# hand_shank.net
KiCad netlist of a schematic drawn in Altium Designer
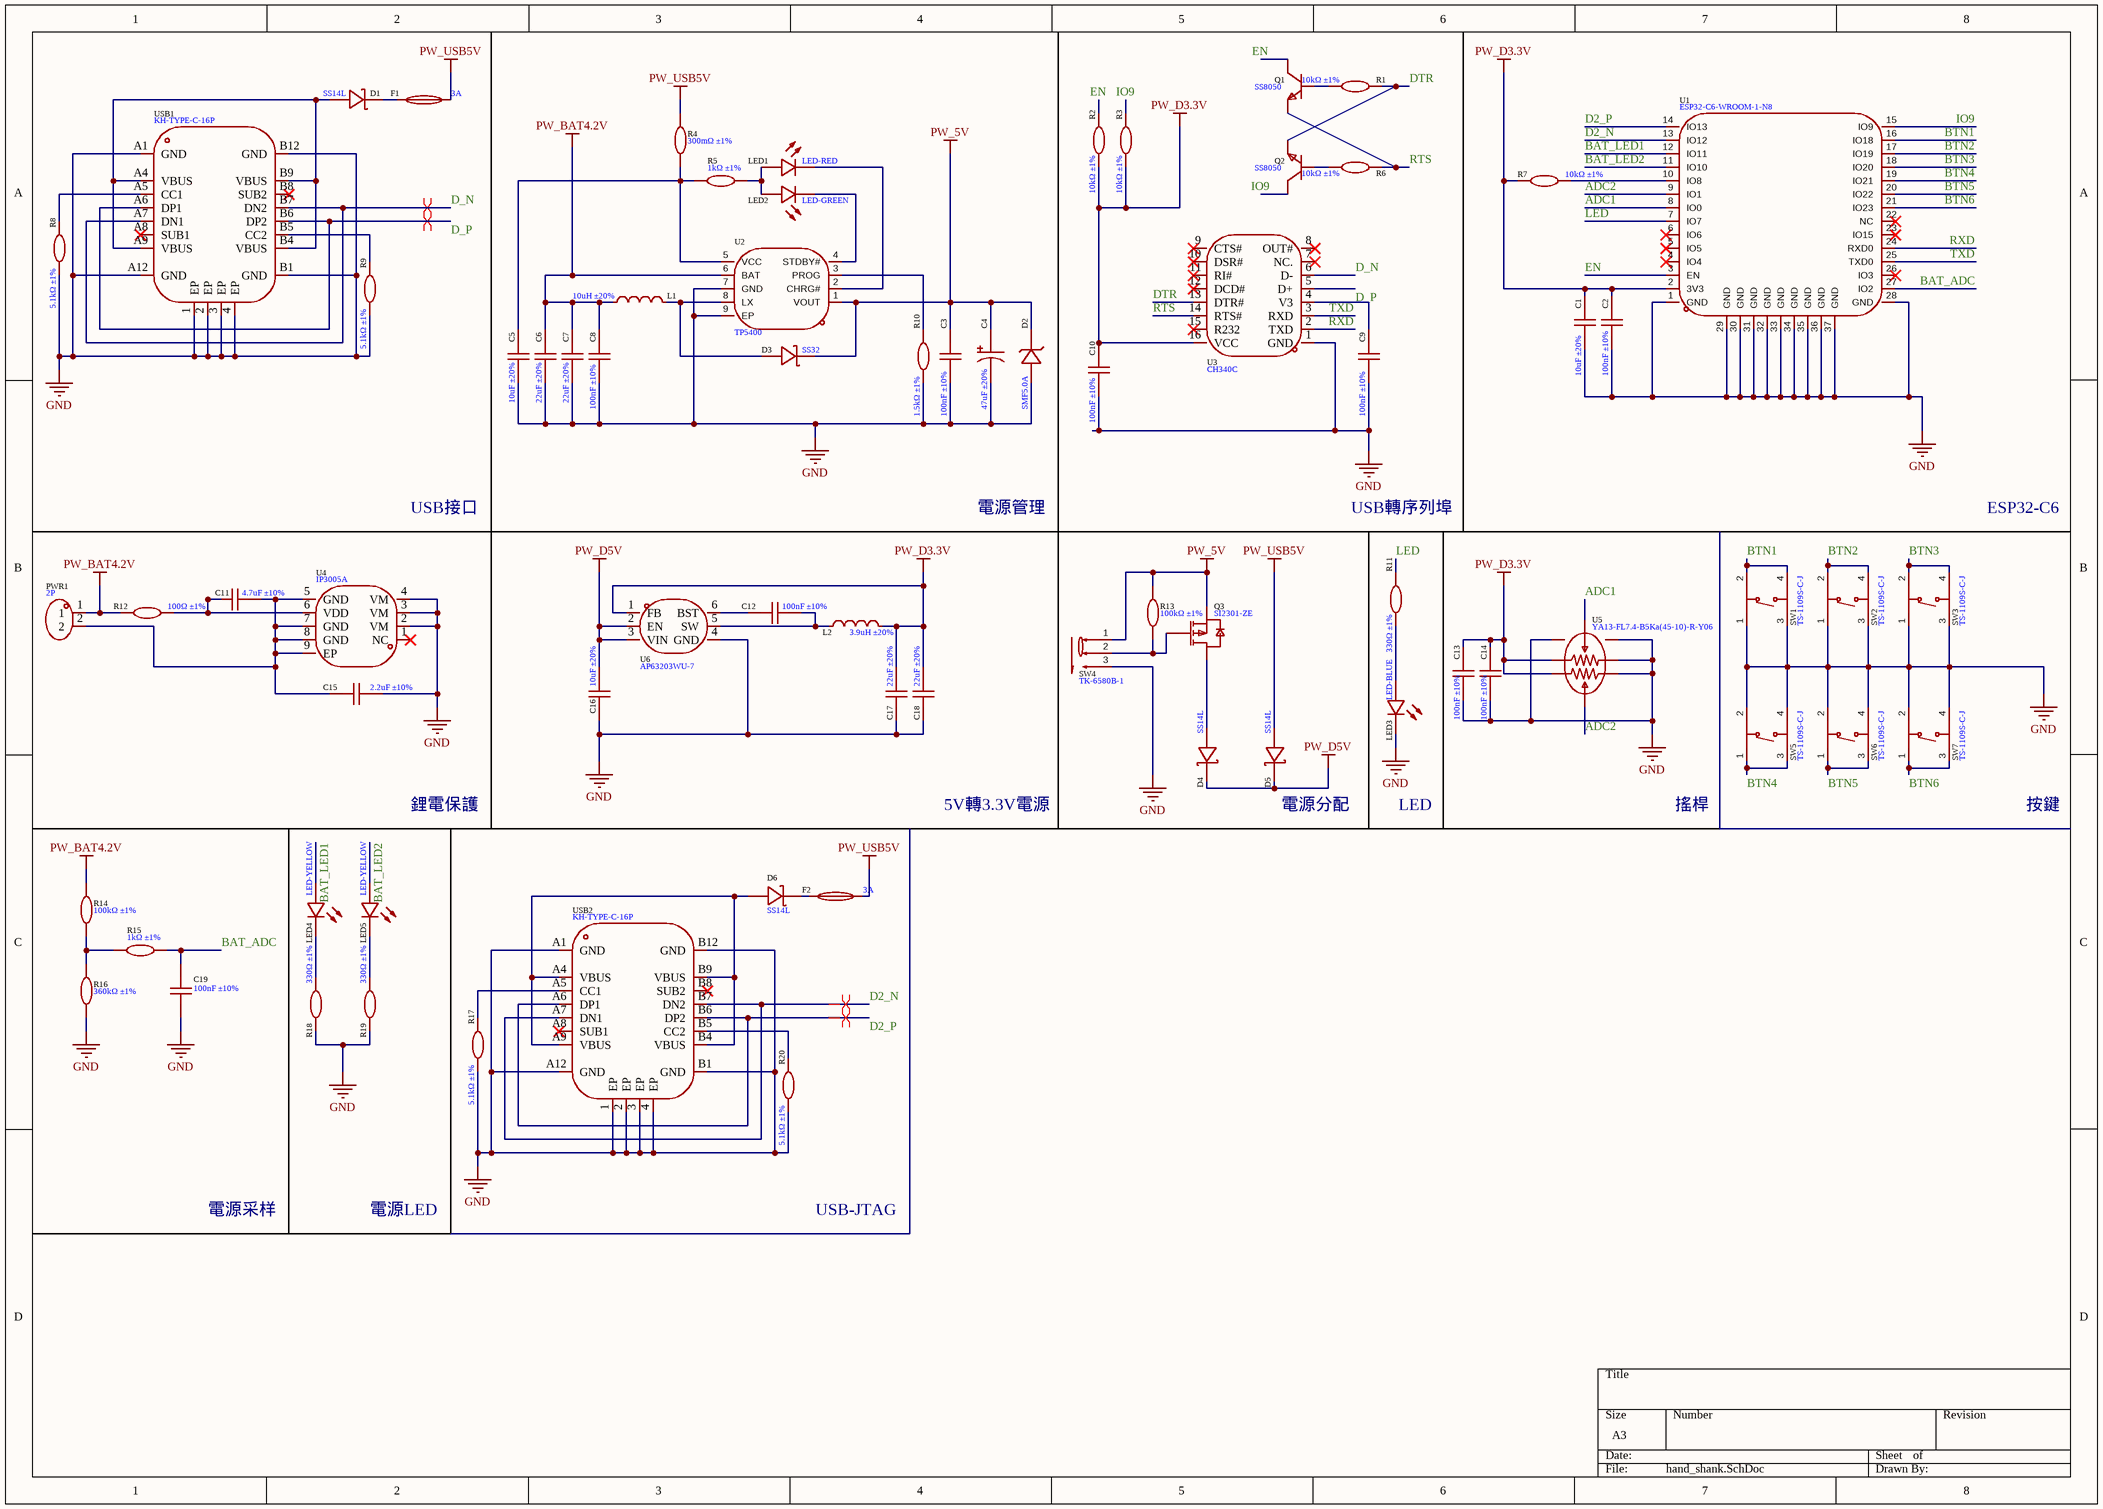
[diagram p0: hand_shank.SchDoc]

(export (version "E")
  (design (tool "Eeschema 10.0.6"))
  (components
    (comp (ref "C1")
      (value "10uF ±20%")
      (footprint "C0603")
      (fields (field (name "MANUFACTURER_PART") "CL10A106MA8NRNC") (field (name "MANUFACTURER") "SAMSUNG"))
      (libsource (lib "Database_Libs") (part "CAP"))
    )
    (comp (ref "C2")
      (value "100nF ±10%")
      (footprint "C0603")
      (fields (field (name "MANUFACTURER_PART") "CL10B104KB8NNNC") (field (name "MANUFACTURER") "SAMSUNG"))
      (libsource (lib "Database_Libs") (part "CAP"))
    )
    (comp (ref "C3")
      (value "100nF ±10%")
      (footprint "C0603")
      (fields (field (name "MANUFACTURER_PART") "CL10B104KB8NNNC") (field (name "MANUFACTURER") "SAMSUNG"))
      (libsource (lib "Database_Libs") (part "CAP"))
    )
    (comp (ref "C4")
      (value "47uF ±20%")
      (footprint "CAP-SMD_BD6.3-L6.5-W6.5-LS7.2-FD")
      (fields (field (name "MANUFACTURER_PART") "RVE25V47M6X5") (field (name "MANUFACTURER") "JIERR"))
      (libsource (lib "Database_Libs") (part "CAP-POL"))
    )
    (comp (ref "C5")
      (value "10uF ±20%")
      (footprint "C0603")
      (fields (field (name "MANUFACTURER_PART") "CL10A106MA8NRNC") (field (name "MANUFACTURER") "SAMSUNG"))
      (libsource (lib "Database_Libs") (part "CAP"))
    )
    (comp (ref "C6")
      (value "22uF ±20%")
      (footprint "C0805")
      (fields (field (name "MANUFACTURER_PART") "CL21A226MAQNNNE") (field (name "MANUFACTURER") "SAMSUNG"))
      (libsource (lib "Database_Libs") (part "CAP"))
    )
    (comp (ref "C7")
      (value "22uF ±20%")
      (footprint "C0805")
      (fields (field (name "MANUFACTURER_PART") "CL21A226MAQNNNE") (field (name "MANUFACTURER") "SAMSUNG"))
      (libsource (lib "Database_Libs") (part "CAP"))
    )
    (comp (ref "C8")
      (value "100nF ±10%")
      (footprint "C0603")
      (fields (field (name "MANUFACTURER_PART") "CL10B104KB8NNNC") (field (name "MANUFACTURER") "SAMSUNG"))
      (libsource (lib "Database_Libs") (part "CAP"))
    )
    (comp (ref "C9")
      (value "100nF ±10%")
      (footprint "C0603")
      (fields (field (name "MANUFACTURER_PART") "CL10B104KB8NNNC") (field (name "MANUFACTURER") "SAMSUNG"))
      (libsource (lib "Database_Libs") (part "CAP"))
    )
    (comp (ref "C10")
      (value "100nF ±10%")
      (footprint "C0603")
      (fields (field (name "MANUFACTURER_PART") "CL10B104KB8NNNC") (field (name "MANUFACTURER") "SAMSUNG"))
      (libsource (lib "Database_Libs") (part "CAP"))
    )
    (comp (ref "C11")
      (value "4.7uF ±10%")
      (footprint "C0603")
      (fields (field (name "MANUFACTURER_PART") "CL10A475KO8NNNC") (field (name "MANUFACTURER") "SAMSUNG"))
      (libsource (lib "Database_Libs") (part "CAP"))
    )
    (comp (ref "C12")
      (value "100nF ±10%")
      (footprint "C0603")
      (fields (field (name "MANUFACTURER_PART") "CL10B104KB8NNNC") (field (name "MANUFACTURER") "SAMSUNG"))
      (libsource (lib "Database_Libs") (part "CAP"))
    )
    (comp (ref "C13")
      (value "100nF ±10%")
      (footprint "C0603")
      (fields (field (name "MANUFACTURER_PART") "CL10B104KB8NNNC") (field (name "MANUFACTURER") "SAMSUNG"))
      (libsource (lib "Database_Libs") (part "CAP"))
    )
    (comp (ref "C14")
      (value "100nF ±10%")
      (footprint "C0603")
      (fields (field (name "MANUFACTURER_PART") "CL10B104KB8NNNC") (field (name "MANUFACTURER") "SAMSUNG"))
      (libsource (lib "Database_Libs") (part "CAP"))
    )
    (comp (ref "C15")
      (value "2.2uF ±10%")
      (footprint "C0603")
      (fields (field (name "MANUFACTURER_PART") "CL10A225KB8NNNC") (field (name "MANUFACTURER") "SAMSUNG"))
      (libsource (lib "Database_Libs") (part "CAP"))
    )
    (comp (ref "C16")
      (value "10uF ±20%")
      (footprint "C0603")
      (fields (field (name "MANUFACTURER_PART") "CL10A106MA8NRNC") (field (name "MANUFACTURER") "SAMSUNG"))
      (libsource (lib "Database_Libs") (part "CAP"))
    )
    (comp (ref "C17")
      (value "22uF ±20%")
      (footprint "C0805")
      (fields (field (name "MANUFACTURER_PART") "CL21A226MAQNNNE") (field (name "MANUFACTURER") "SAMSUNG"))
      (libsource (lib "Database_Libs") (part "CAP"))
    )
    (comp (ref "C18")
      (value "22uF ±20%")
      (footprint "C0805")
      (fields (field (name "MANUFACTURER_PART") "CL21A226MAQNNNE") (field (name "MANUFACTURER") "SAMSUNG"))
      (libsource (lib "Database_Libs") (part "CAP"))
    )
    (comp (ref "C19")
      (value "100nF ±10%")
      (footprint "C0603")
      (fields (field (name "MANUFACTURER_PART") "CL10B104KB8NNNC") (field (name "MANUFACTURER") "SAMSUNG"))
      (libsource (lib "Database_Libs") (part "CAP"))
    )
    (comp (ref "D1")
      (value "SS14L")
      (footprint "SOD-123F_L2.8-W1.8-LS3.7-RD")
      (fields (field (name "MANUFACTURER") "Hottech"))
      (libsource (lib "Database_Libs") (part "DIODE-SCHOTTKY"))
    )
    (comp (ref "D2")
      (value "SMF5.0A")
      (footprint "SOD-123FL_L2.7-W1.8-LS3.8-RD")
      (fields (field (name "MANUFACTURER") "R+O"))
      (libsource (lib "Database_Libs") (part "DIODE-TVS"))
    )
    (comp (ref "D3")
      (value "SS32")
      (footprint "SMA_L4.3-W2.6-LS5.0-RD")
      (fields (field (name "MANUFACTURER") "R+O"))
      (libsource (lib "Database_Libs") (part "DIODE-SCHOTTKY"))
    )
    (comp (ref "D4")
      (value "SS14L")
      (footprint "SOD-123F_L2.8-W1.8-LS3.7-RD")
      (fields (field (name "MANUFACTURER") "Hottech"))
      (libsource (lib "Database_Libs") (part "DIODE-SCHOTTKY"))
    )
    (comp (ref "D5")
      (value "SS14L")
      (footprint "SOD-123F_L2.8-W1.8-LS3.7-RD")
      (fields (field (name "MANUFACTURER") "Hottech"))
      (libsource (lib "Database_Libs") (part "DIODE-SCHOTTKY"))
    )
    (comp (ref "D6")
      (value "SS14L")
      (footprint "SOD-123F_L2.8-W1.8-LS3.7-RD")
      (fields (field (name "MANUFACTURER") "Hottech"))
      (libsource (lib "Database_Libs") (part "DIODE-SCHOTTKY"))
    )
    (comp (ref "F1")
      (value "3A")
      (footprint "F1206")
      (fields (field (name "MANUFACTURER_PART") "12H1300C") (field (name "MANUFACTURER") "LANSON"))
      (libsource (lib "Database_Libs") (part "FUSE"))
    )
    (comp (ref "F2")
      (value "3A")
      (footprint "F1206")
      (fields (field (name "MANUFACTURER_PART") "12H1300C") (field (name "MANUFACTURER") "LANSON"))
      (libsource (lib "Database_Libs") (part "FUSE"))
    )
    (comp (ref "L1")
      (value "10uH ±20%")
      (footprint "IND-SMD_L7.3-W6.8")
      (fields (field (name "MANUFACTURER_PART") "FXL0630-100-M") (field (name "MANUFACTURER") "cjiang"))
      (libsource (lib "Database_Libs") (part "IND"))
    )
    (comp (ref "L2")
      (value "3.9uH ±20%")
      (footprint "IND-SMD_L4.0-W4.0_FNR40XXS")
      (fields (field (name "MANUFACTURER_PART") "FNR4030S3R9MT") (field (name "MANUFACTURER") "cjiang"))
      (libsource (lib "Database_Libs") (part "IND"))
    )
    (comp (ref "LED1")
      (value "LED-RED")
      (footprint "LED0603-RD")
      (fields (field (name "MANUFACTURER_PART") "NCD0603R1") (field (name "MANUFACTURER") "nationstar"))
      (libsource (lib "Database_Libs") (part "LED"))
    )
    (comp (ref "LED2")
      (value "LED-GREEN")
      (footprint "LED0603-RD")
      (fields (field (name "MANUFACTURER_PART") "NCD0603G1") (field (name "MANUFACTURER") "nationstar"))
      (libsource (lib "Database_Libs") (part "LED"))
    )
    (comp (ref "LED3")
      (value "LED-BLUE")
      (footprint "LED0603-RD")
      (fields (field (name "MANUFACTURER_PART") "NCD0603B1") (field (name "MANUFACTURER") "nationstar"))
      (libsource (lib "Database_Libs") (part "LED"))
    )
    (comp (ref "LED4")
      (value "LED-YELLOW")
      (footprint "LED0603-RD")
      (fields (field (name "MANUFACTURER_PART") "NCD0603Y1") (field (name "MANUFACTURER") "nationstar"))
      (libsource (lib "Database_Libs") (part "LED"))
    )
    (comp (ref "LED5")
      (value "LED-YELLOW")
      (footprint "LED0603-RD")
      (fields (field (name "MANUFACTURER_PART") "NCD0603Y1") (field (name "MANUFACTURER") "nationstar"))
      (libsource (lib "Database_Libs") (part "LED"))
    )
    (comp (ref "PWR1")
      (value "2P")
      (footprint "CONN-TH_HC-C5080-2AS")
      (fields (field (name "MANUFACTURER_PART") "HC-C5080-2AS") (field (name "MANUFACTURER") "HCTL"))
      (libsource (lib "Database_Libs") (part "CONN-power-2P"))
    )
    (comp (ref "Q1")
      (value "SS8050")
      (footprint "SOT-23-3")
      (fields (field (name "MANUFACTURER") "AnBon"))
      (libsource (lib "Database_Libs") (part "NPN-1B2E3C"))
    )
    (comp (ref "Q2")
      (value "SS8050")
      (footprint "SOT-23-3")
      (fields (field (name "MANUFACTURER") "AnBon"))
      (libsource (lib "Database_Libs") (part "NPN-1B2E3C"))
    )
    (comp (ref "Q3")
      (value "SI2301-ZE")
      (footprint "SOT-23-3")
      (fields (field (name "MANUFACTURER") "HXY"))
      (libsource (lib "Database_Libs") (part "PMOS-1G2S3D"))
    )
    (comp (ref "R1")
      (value "10kΩ ±1%")
      (footprint "R0603")
      (fields (field (name "MANUFACTURER_PART") "0603WAF1002T5E") (field (name "MANUFACTURER") "UNI-ROYAL"))
      (libsource (lib "Database_Libs") (part "RES"))
    )
    (comp (ref "R2")
      (value "10kΩ ±1%")
      (footprint "R0603")
      (fields (field (name "MANUFACTURER_PART") "0603WAF1002T5E") (field (name "MANUFACTURER") "UNI-ROYAL"))
      (libsource (lib "Database_Libs") (part "RES"))
    )
    (comp (ref "R3")
      (value "10kΩ ±1%")
      (footprint "R0603")
      (fields (field (name "MANUFACTURER_PART") "0603WAF1002T5E") (field (name "MANUFACTURER") "UNI-ROYAL"))
      (libsource (lib "Database_Libs") (part "RES"))
    )
    (comp (ref "R4")
      (value "300mΩ ±1%")
      (footprint "R1206")
      (fields
        (field (name "MANUFACTURER_PART") "HoYH1206-1W-300mR-1%")
        (field (name "MANUFACTURER") "Milliohm")
      )
      (libsource (lib "Database_Libs") (part "RES"))
    )
    (comp (ref "R5")
      (value "1kΩ ±1%")
      (footprint "R0603")
      (fields (field (name "MANUFACTURER_PART") "0603WAF1001T5E") (field (name "MANUFACTURER") "UNI-ROYAL"))
      (libsource (lib "Database_Libs") (part "RES"))
    )
    (comp (ref "R6")
      (value "10kΩ ±1%")
      (footprint "R0603")
      (fields (field (name "MANUFACTURER_PART") "0603WAF1002T5E") (field (name "MANUFACTURER") "UNI-ROYAL"))
      (libsource (lib "Database_Libs") (part "RES"))
    )
    (comp (ref "R7")
      (value "10kΩ ±1%")
      (footprint "R0603")
      (fields (field (name "MANUFACTURER_PART") "0603WAF1002T5E") (field (name "MANUFACTURER") "UNI-ROYAL"))
      (libsource (lib "Database_Libs") (part "RES"))
    )
    (comp (ref "R8")
      (value "5.1kΩ ±1%")
      (footprint "R0603")
      (fields (field (name "MANUFACTURER_PART") "0603WAF5101T5E") (field (name "MANUFACTURER") "UNI-ROYAL"))
      (libsource (lib "Database_Libs") (part "RES"))
    )
    (comp (ref "R9")
      (value "5.1kΩ ±1%")
      (footprint "R0603")
      (fields (field (name "MANUFACTURER_PART") "0603WAF5101T5E") (field (name "MANUFACTURER") "UNI-ROYAL"))
      (libsource (lib "Database_Libs") (part "RES"))
    )
    (comp (ref "R10")
      (value "1.5kΩ ±1%")
      (footprint "R0603")
      (fields (field (name "MANUFACTURER_PART") "0603WAF1501T5E") (field (name "MANUFACTURER") "UNI-ROYAL"))
      (libsource (lib "Database_Libs") (part "RES"))
    )
    (comp (ref "R11")
      (value "330Ω ±1%")
      (footprint "R0603")
      (fields (field (name "MANUFACTURER_PART") "0603WAF3300T5E") (field (name "MANUFACTURER") "UNI-ROYAL"))
      (libsource (lib "Database_Libs") (part "RES"))
    )
    (comp (ref "R12")
      (value "100Ω ±1%")
      (footprint "R0603")
      (fields (field (name "MANUFACTURER_PART") "0603WAF1000T5E") (field (name "MANUFACTURER") "UNI-ROYAL"))
      (libsource (lib "Database_Libs") (part "RES"))
    )
    (comp (ref "R13")
      (value "100kΩ ±1%")
      (footprint "R0603")
      (fields (field (name "MANUFACTURER_PART") "0603WAF1003T5E") (field (name "MANUFACTURER") "UNI-ROYAL"))
      (libsource (lib "Database_Libs") (part "RES"))
    )
    (comp (ref "R14")
      (value "100kΩ ±1%")
      (footprint "R0603")
      (fields (field (name "MANUFACTURER_PART") "0603WAF1003T5E") (field (name "MANUFACTURER") "UNI-ROYAL"))
      (libsource (lib "Database_Libs") (part "RES"))
    )
    (comp (ref "R15")
      (value "1kΩ ±1%")
      (footprint "R0603")
      (fields (field (name "MANUFACTURER_PART") "0603WAF1001T5E") (field (name "MANUFACTURER") "UNI-ROYAL"))
      (libsource (lib "Database_Libs") (part "RES"))
    )
    (comp (ref "R16")
      (value "360kΩ ±1%")
      (footprint "R0603")
      (fields (field (name "MANUFACTURER_PART") "0603WAF3603T5E") (field (name "MANUFACTURER") "UNI-ROYAL"))
      (libsource (lib "Database_Libs") (part "RES"))
    )
    (comp (ref "R17")
      (value "5.1kΩ ±1%")
      (footprint "R0603")
      (fields (field (name "MANUFACTURER_PART") "0603WAF5101T5E") (field (name "MANUFACTURER") "UNI-ROYAL"))
      (libsource (lib "Database_Libs") (part "RES"))
    )
    (comp (ref "R18")
      (value "330Ω ±1%")
      (footprint "R0603")
      (fields (field (name "MANUFACTURER_PART") "0603WAF3300T5E") (field (name "MANUFACTURER") "UNI-ROYAL"))
      (libsource (lib "Database_Libs") (part "RES"))
    )
    (comp (ref "R19")
      (value "330Ω ±1%")
      (footprint "R0603")
      (fields (field (name "MANUFACTURER_PART") "0603WAF3300T5E") (field (name "MANUFACTURER") "UNI-ROYAL"))
      (libsource (lib "Database_Libs") (part "RES"))
    )
    (comp (ref "R20")
      (value "5.1kΩ ±1%")
      (footprint "R0603")
      (fields (field (name "MANUFACTURER_PART") "0603WAF5101T5E") (field (name "MANUFACTURER") "UNI-ROYAL"))
      (libsource (lib "Database_Libs") (part "RES"))
    )
    (comp (ref "SW1")
      (value "TS-1109S-C-J")
      (footprint "SW-SMD_4P-L4.5-W4.5-P3.00-LS7.0")
      (fields (field (name "MANUFACTURER") "XKB Connection"))
      (libsource (lib "Database_Libs") (part "SW-PTS-2x2"))
    )
    (comp (ref "SW2")
      (value "TS-1109S-C-J")
      (footprint "SW-SMD_4P-L4.5-W4.5-P3.00-LS7.0")
      (fields (field (name "MANUFACTURER") "XKB Connection"))
      (libsource (lib "Database_Libs") (part "SW-PTS-2x2"))
    )
    (comp (ref "SW3")
      (value "TS-1109S-C-J")
      (footprint "SW-SMD_4P-L4.5-W4.5-P3.00-LS7.0")
      (fields (field (name "MANUFACTURER") "XKB Connection"))
      (libsource (lib "Database_Libs") (part "SW-PTS-2x2"))
    )
    (comp (ref "SW4")
      (value "TK-6580B-1")
      (footprint "SW-TH_TK-6580B-1")
      (fields (field (name "MANUFACTURER") "Yuandi"))
      (libsource (lib "Database_Libs") (part "SW-SPDT-1x3"))
    )
    (comp (ref "SW5")
      (value "TS-1109S-C-J")
      (footprint "SW-SMD_4P-L4.5-W4.5-P3.00-LS7.0")
      (fields (field (name "MANUFACTURER") "XKB Connection"))
      (libsource (lib "Database_Libs") (part "SW-PTS-2x2"))
    )
    (comp (ref "SW6")
      (value "TS-1109S-C-J")
      (footprint "SW-SMD_4P-L4.5-W4.5-P3.00-LS7.0")
      (fields (field (name "MANUFACTURER") "XKB Connection"))
      (libsource (lib "Database_Libs") (part "SW-PTS-2x2"))
    )
    (comp (ref "SW7")
      (value "TS-1109S-C-J")
      (footprint "SW-SMD_4P-L4.5-W4.5-P3.00-LS7.0")
      (fields (field (name "MANUFACTURER") "XKB Connection"))
      (libsource (lib "Database_Libs") (part "SW-PTS-2x2"))
    )
    (comp (ref "U1")
      (value "ESP32-C6-WROOM-1-N8")
      (footprint "WIRELM-SMD_ESP32-C6-WROOM-1")
      (fields (field (name "MANUFACTURER") "ESPRESSIF"))
      (libsource (lib "Database_Libs") (part "ESP32-C6-WROOM"))
    )
    (comp (ref "U2")
      (value "TP5400")
      (footprint "ESOP-8_L4.9-W3.9-P1.27-LS6.0-BL-EP")
      (fields (field (name "MANUFACTURER") "TOPPOWER"))
      (libsource (lib "Database_Libs") (part "TP5400"))
    )
    (comp (ref "U3")
      (value "CH340C")
      (footprint "SOP-16_L10.0-W3.9-P1.27-LS6.0-BL")
      (fields (field (name "MANUFACTURER") "WCH"))
      (libsource (lib "Database_Libs") (part "CH340C"))
    )
    (comp (ref "U4")
      (value "IP3005A")
      (footprint "ESOP-8_L4.9-W3.9-P1.27-LS6.0-BL-EP")
      (fields (field (name "MANUFACTURER") "INJOINIC"))
      (libsource (lib "Database_Libs") (part "IP3005A"))
    )
    (comp (ref "U5")
      (value "YA13-FL7.4-B5Ka(45-10)-R-Y06")
      (footprint "RES-ADJ-TH_YA13-FL7.4-B5KA-45-10-R-Y06_1")
      (fields (field (name "MANUFACTURER") "YTL"))
      (libsource (lib "Database_Libs") (part "YA13-FL7.4-B5KA(45-10)-R-Y06"))
    )
    (comp (ref "U6")
      (value "AP63203WU-7")
      (footprint "TSOT-26_L2.9-W1.6-P0.95-LS2.8-BL")
      (fields (field (name "MANUFACTURER") "DIODES"))
      (libsource (lib "Database_Libs") (part "AP63203WU-7"))
    )
    (comp (ref "USB1")
      (value "KH-TYPE-C-16P")
      (footprint "USB-C-SMD_KH-TYPE-C-16P")
      (fields (field (name "MANUFACTURER") "kinghelm"))
      (libsource (lib "Database_Libs") (part "CONN-USBC-16P"))
    )
    (comp (ref "USB2")
      (value "KH-TYPE-C-16P")
      (footprint "USB-C-SMD_KH-TYPE-C-16P")
      (fields (field (name "MANUFACTURER") "kinghelm"))
      (libsource (lib "Database_Libs") (part "CONN-USBC-16P"))
    )
  )
  (nets
    (net (code "1") (name "/ADC1") (class "Default")
      (node (ref "U1") (pin "8") (pinfunction "IO0_8") (pintype "passive"))
      (node (ref "U5") (pin "2") (pinfunction "2_2") (pintype "passive"))
    )
    (net (code "2") (name "/ADC2") (class "Default")
      (node (ref "U1") (pin "9") (pinfunction "IO1_9") (pintype "passive"))
      (node (ref "U5") (pin "5") (pinfunction "5_5") (pintype "passive"))
    )
    (net (code "3") (name "/BAT_ADC") (class "Default")
      (node (ref "C19") (pin "2") (pinfunction "2_2") (pintype "passive"))
      (node (ref "R15") (pin "2") (pinfunction "2_2") (pintype "passive"))
      (node (ref "U1") (pin "27") (pinfunction "IO2_27") (pintype "passive"))
    )
    (net (code "4") (name "/BAT_LED1") (class "Default")
      (node (ref "LED4") (pin "2") (pinfunction "A_2") (pintype "passive"))
      (node (ref "U1") (pin "12") (pinfunction "IO11_12") (pintype "passive"))
    )
    (net (code "5") (name "/BAT_LED2") (class "Default")
      (node (ref "LED5") (pin "2") (pinfunction "A_2") (pintype "passive"))
      (node (ref "U1") (pin "11") (pinfunction "IO10_11") (pintype "passive"))
    )
    (net (code "6") (name "/BTN1") (class "Default")
      (node (ref "SW1") (pin "2") (pinfunction "2_2") (pintype "passive"))
      (node (ref "SW1") (pin "4") (pinfunction "4_4") (pintype "passive"))
      (node (ref "U1") (pin "16") (pinfunction "IO18_16") (pintype "passive"))
    )
    (net (code "7") (name "/BTN2") (class "Default")
      (node (ref "SW2") (pin "2") (pinfunction "2_2") (pintype "passive"))
      (node (ref "SW2") (pin "4") (pinfunction "4_4") (pintype "passive"))
      (node (ref "U1") (pin "17") (pinfunction "IO19_17") (pintype "passive"))
    )
    (net (code "8") (name "/BTN3") (class "Default")
      (node (ref "SW3") (pin "2") (pinfunction "2_2") (pintype "passive"))
      (node (ref "SW3") (pin "4") (pinfunction "4_4") (pintype "passive"))
      (node (ref "U1") (pin "18") (pinfunction "IO20_18") (pintype "passive"))
    )
    (net (code "9") (name "/BTN4") (class "Default")
      (node (ref "SW5") (pin "1") (pinfunction "1_1") (pintype "passive"))
      (node (ref "SW5") (pin "3") (pinfunction "3_3") (pintype "passive"))
      (node (ref "U1") (pin "19") (pinfunction "IO21_19") (pintype "passive"))
    )
    (net (code "10") (name "/BTN5") (class "Default")
      (node (ref "SW6") (pin "1") (pinfunction "1_1") (pintype "passive"))
      (node (ref "SW6") (pin "3") (pinfunction "3_3") (pintype "passive"))
      (node (ref "U1") (pin "20") (pinfunction "IO22_20") (pintype "passive"))
    )
    (net (code "11") (name "/BTN6") (class "Default")
      (node (ref "SW7") (pin "1") (pinfunction "1_1") (pintype "passive"))
      (node (ref "SW7") (pin "3") (pinfunction "3_3") (pintype "passive"))
      (node (ref "U1") (pin "21") (pinfunction "IO23_21") (pintype "passive"))
    )
    (net (code "12") (name "/D2_N") (class "Default")
      (node (ref "U1") (pin "13") (pinfunction "IO12_13") (pintype "passive"))
      (node (ref "USB2") (pin "A7") (pinfunction "DN1_A7") (pintype "passive"))
      (node (ref "USB2") (pin "B7") (pinfunction "DN2_B7") (pintype "passive"))
    )
    (net (code "13") (name "/D2_P") (class "Default")
      (node (ref "U1") (pin "14") (pinfunction "IO13_14") (pintype "passive"))
      (node (ref "USB2") (pin "A6") (pinfunction "DP1_A6") (pintype "passive"))
      (node (ref "USB2") (pin "B6") (pinfunction "DP2_B6") (pintype "passive"))
    )
    (net (code "14") (name "/DTR") (class "Default")
      (node (ref "Q2") (pin "2") (pinfunction "E_2") (pintype "passive"))
      (node (ref "R1") (pin "2") (pinfunction "2_2") (pintype "passive"))
      (node (ref "U3") (pin "13") (pinfunction "DTR#_13") (pintype "passive"))
    )
    (net (code "15") (name "/D_N") (class "Default")
      (node (ref "U3") (pin "6") (pinfunction "D-_6") (pintype "passive"))
      (node (ref "USB1") (pin "A7") (pinfunction "DN1_A7") (pintype "passive"))
      (node (ref "USB1") (pin "B7") (pinfunction "DN2_B7") (pintype "passive"))
    )
    (net (code "16") (name "/D_P") (class "Default")
      (node (ref "U3") (pin "5") (pinfunction "D+_5") (pintype "passive"))
      (node (ref "USB1") (pin "A6") (pinfunction "DP1_A6") (pintype "passive"))
      (node (ref "USB1") (pin "B6") (pinfunction "DP2_B6") (pintype "passive"))
    )
    (net (code "17") (name "/EN") (class "Default")
      (node (ref "Q1") (pin "3") (pinfunction "C_3") (pintype "passive"))
      (node (ref "R2") (pin "2") (pinfunction "2_2") (pintype "passive"))
      (node (ref "U1") (pin "3") (pinfunction "EN_3") (pintype "passive"))
    )
    (net (code "18") (name "/IO9") (class "Default")
      (node (ref "Q2") (pin "3") (pinfunction "C_3") (pintype "passive"))
      (node (ref "R3") (pin "2") (pinfunction "2_2") (pintype "passive"))
      (node (ref "U1") (pin "15") (pinfunction "IO9_15") (pintype "passive"))
    )
    (net (code "19") (name "/LED") (class "Default")
      (node (ref "R11") (pin "2") (pinfunction "2_2") (pintype "passive"))
      (node (ref "U1") (pin "7") (pinfunction "IO7_7") (pintype "passive"))
    )
    (net (code "20") (name "/RTS") (class "Default")
      (node (ref "Q1") (pin "2") (pinfunction "E_2") (pintype "passive"))
      (node (ref "R6") (pin "2") (pinfunction "2_2") (pintype "passive"))
      (node (ref "U3") (pin "14") (pinfunction "RTS#_14") (pintype "passive"))
    )
    (net (code "21") (name "/RXD") (class "Default")
      (node (ref "U1") (pin "24") (pinfunction "RXD0_24") (pintype "passive"))
      (node (ref "U3") (pin "2") (pinfunction "TXD_2") (pintype "passive"))
    )
    (net (code "22") (name "/TXD") (class "Default")
      (node (ref "U1") (pin "25") (pinfunction "TXD0_25") (pintype "passive"))
      (node (ref "U3") (pin "3") (pinfunction "RXD_3") (pintype "passive"))
    )
    (net (code "23") (name "GND") (class "Default")
      (node (ref "C1") (pin "1") (pinfunction "1_1") (pintype "passive"))
      (node (ref "C10") (pin "1") (pinfunction "1_1") (pintype "passive"))
      (node (ref "C13") (pin "1") (pinfunction "1_1") (pintype "passive"))
      (node (ref "C14") (pin "1") (pinfunction "1_1") (pintype "passive"))
      (node (ref "C15") (pin "2") (pinfunction "2_2") (pintype "passive"))
      (node (ref "C16") (pin "2") (pinfunction "2_2") (pintype "passive"))
      (node (ref "C17") (pin "1") (pinfunction "1_1") (pintype "passive"))
      (node (ref "C18") (pin "1") (pinfunction "1_1") (pintype "passive"))
      (node (ref "C19") (pin "1") (pinfunction "1_1") (pintype "passive"))
      (node (ref "C2") (pin "1") (pinfunction "1_1") (pintype "passive"))
      (node (ref "C3") (pin "1") (pinfunction "1_1") (pintype "passive"))
      (node (ref "C4") (pin "2") (pinfunction "2_2") (pintype "passive"))
      (node (ref "C5") (pin "1") (pinfunction "1_1") (pintype "passive"))
      (node (ref "C6") (pin "1") (pinfunction "1_1") (pintype "passive"))
      (node (ref "C7") (pin "1") (pinfunction "1_1") (pintype "passive"))
      (node (ref "C8") (pin "2") (pinfunction "2_2") (pintype "passive"))
      (node (ref "C9") (pin "1") (pinfunction "1_1") (pintype "passive"))
      (node (ref "D2") (pin "2") (pinfunction "A_2") (pintype "passive"))
      (node (ref "LED3") (pin "1") (pinfunction "K_1") (pintype "passive"))
      (node (ref "R10") (pin "1") (pinfunction "1_1") (pintype "passive"))
      (node (ref "R16") (pin "2") (pinfunction "2_2") (pintype "passive"))
      (node (ref "R17") (pin "1") (pinfunction "1_1") (pintype "passive"))
      (node (ref "R18") (pin "1") (pinfunction "1_1") (pintype "passive"))
      (node (ref "R19") (pin "1") (pinfunction "1_1") (pintype "passive"))
      (node (ref "R20") (pin "1") (pinfunction "1_1") (pintype "passive"))
      (node (ref "R8") (pin "1") (pinfunction "1_1") (pintype "passive"))
      (node (ref "R9") (pin "1") (pinfunction "1_1") (pintype "passive"))
      (node (ref "SW1") (pin "1") (pinfunction "1_1") (pintype "passive"))
      (node (ref "SW1") (pin "3") (pinfunction "3_3") (pintype "passive"))
      (node (ref "SW2") (pin "1") (pinfunction "1_1") (pintype "passive"))
      (node (ref "SW2") (pin "3") (pinfunction "3_3") (pintype "passive"))
      (node (ref "SW3") (pin "1") (pinfunction "1_1") (pintype "passive"))
      (node (ref "SW3") (pin "3") (pinfunction "3_3") (pintype "passive"))
      (node (ref "SW4") (pin "3") (pinfunction "3_3") (pintype "passive"))
      (node (ref "SW5") (pin "2") (pinfunction "2_2") (pintype "passive"))
      (node (ref "SW5") (pin "4") (pinfunction "4_4") (pintype "passive"))
      (node (ref "SW6") (pin "2") (pinfunction "2_2") (pintype "passive"))
      (node (ref "SW6") (pin "4") (pinfunction "4_4") (pintype "passive"))
      (node (ref "SW7") (pin "2") (pinfunction "2_2") (pintype "passive"))
      (node (ref "SW7") (pin "4") (pinfunction "4_4") (pintype "passive"))
      (node (ref "U1") (pin "1") (pinfunction "GND_1") (pintype "passive"))
      (node (ref "U1") (pin "28") (pinfunction "GND_28") (pintype "passive"))
      (node (ref "U1") (pin "29") (pinfunction "GND_29") (pintype "passive"))
      (node (ref "U1") (pin "30") (pinfunction "GND_30") (pintype "passive"))
      (node (ref "U1") (pin "31") (pinfunction "GND_31") (pintype "passive"))
      (node (ref "U1") (pin "32") (pinfunction "GND_32") (pintype "passive"))
      (node (ref "U1") (pin "33") (pinfunction "GND_33") (pintype "passive"))
      (node (ref "U1") (pin "34") (pinfunction "GND_34") (pintype "passive"))
      (node (ref "U1") (pin "35") (pinfunction "GND_35") (pintype "passive"))
      (node (ref "U1") (pin "36") (pinfunction "GND_36") (pintype "passive"))
      (node (ref "U1") (pin "37") (pinfunction "GND_37") (pintype "passive"))
      (node (ref "U2") (pin "7") (pinfunction "GND_7") (pintype "passive"))
      (node (ref "U2") (pin "9") (pinfunction "EP_9") (pintype "passive"))
      (node (ref "U3") (pin "1") (pinfunction "GND_1") (pintype "passive"))
      (node (ref "U4") (pin "2") (pinfunction "VM_2") (pintype "passive"))
      (node (ref "U4") (pin "3") (pinfunction "VM_3") (pintype "passive"))
      (node (ref "U4") (pin "4") (pinfunction "VM_4") (pintype "passive"))
      (node (ref "U5") (pin "1") (pinfunction "1_1") (pintype "passive"))
      (node (ref "U5") (pin "4") (pinfunction "4_4") (pintype "passive"))
      (node (ref "U5") (pin "7") (pinfunction "7_7") (pintype "passive"))
      (node (ref "U5") (pin "8") (pinfunction "8_8") (pintype "passive"))
      (node (ref "U6") (pin "4") (pinfunction "GND_4") (pintype "passive"))
      (node (ref "USB1") (pin "1") (pinfunction "EP_1") (pintype "passive"))
      (node (ref "USB1") (pin "2") (pinfunction "EP_2") (pintype "passive"))
      (node (ref "USB1") (pin "3") (pinfunction "EP_3") (pintype "passive"))
      (node (ref "USB1") (pin "4") (pinfunction "EP_4") (pintype "passive"))
      (node (ref "USB1") (pin "A1") (pinfunction "GND_A1") (pintype "passive"))
      (node (ref "USB1") (pin "A12") (pinfunction "GND_A12") (pintype "passive"))
      (node (ref "USB1") (pin "B1") (pinfunction "GND_B1") (pintype "passive"))
      (node (ref "USB1") (pin "B12") (pinfunction "GND_B12") (pintype "passive"))
      (node (ref "USB2") (pin "1") (pinfunction "EP_1") (pintype "passive"))
      (node (ref "USB2") (pin "2") (pinfunction "EP_2") (pintype "passive"))
      (node (ref "USB2") (pin "3") (pinfunction "EP_3") (pintype "passive"))
      (node (ref "USB2") (pin "4") (pinfunction "EP_4") (pintype "passive"))
      (node (ref "USB2") (pin "A1") (pinfunction "GND_A1") (pintype "passive"))
      (node (ref "USB2") (pin "A12") (pinfunction "GND_A12") (pintype "passive"))
      (node (ref "USB2") (pin "B1") (pinfunction "GND_B1") (pintype "passive"))
      (node (ref "USB2") (pin "B12") (pinfunction "GND_B12") (pintype "passive"))
    )
    (net (code "24") (name "Net-(D1-A)") (class "Default")
      (node (ref "D1") (pin "2") (pinfunction "A_2") (pintype "passive"))
      (node (ref "USB1") (pin "A4") (pinfunction "VBUS_A4") (pintype "passive"))
      (node (ref "USB1") (pin "A9") (pinfunction "VBUS_A9") (pintype "passive"))
      (node (ref "USB1") (pin "B4") (pinfunction "VBUS_B4") (pintype "passive"))
      (node (ref "USB1") (pin "B9") (pinfunction "VBUS_B9") (pintype "passive"))
    )
    (net (code "25") (name "Net-(D1-K)") (class "Default")
      (node (ref "D1") (pin "1") (pinfunction "K_1") (pintype "passive"))
      (node (ref "F1") (pin "1") (pinfunction "1_1") (pintype "passive"))
    )
    (net (code "26") (name "Net-(D3-A)") (class "Default")
      (node (ref "D3") (pin "2") (pinfunction "A_2") (pintype "passive"))
      (node (ref "L1") (pin "2") (pinfunction "2_2") (pintype "passive"))
      (node (ref "U2") (pin "8") (pinfunction "LX_8") (pintype "passive"))
    )
    (net (code "27") (name "Net-(D4-A)") (class "Default")
      (node (ref "D4") (pin "2") (pinfunction "A_2") (pintype "passive"))
      (node (ref "Q3") (pin "3") (pinfunction "D_3") (pintype "passive"))
    )
    (net (code "28") (name "Net-(D6-A)") (class "Default")
      (node (ref "D6") (pin "2") (pinfunction "A_2") (pintype "passive"))
      (node (ref "USB2") (pin "A4") (pinfunction "VBUS_A4") (pintype "passive"))
      (node (ref "USB2") (pin "A9") (pinfunction "VBUS_A9") (pintype "passive"))
      (node (ref "USB2") (pin "B4") (pinfunction "VBUS_B4") (pintype "passive"))
      (node (ref "USB2") (pin "B9") (pinfunction "VBUS_B9") (pintype "passive"))
    )
    (net (code "29") (name "Net-(D6-K)") (class "Default")
      (node (ref "D6") (pin "1") (pinfunction "K_1") (pintype "passive"))
      (node (ref "F2") (pin "1") (pinfunction "1_1") (pintype "passive"))
    )
    (net (code "30") (name "Net-(LED1-A)") (class "Default")
      (node (ref "LED1") (pin "2") (pinfunction "A_2") (pintype "passive"))
      (node (ref "LED2") (pin "2") (pinfunction "A_2") (pintype "passive"))
      (node (ref "R5") (pin "1") (pinfunction "1_1") (pintype "passive"))
    )
    (net (code "31") (name "Net-(LED1-K)") (class "Default")
      (node (ref "LED1") (pin "1") (pinfunction "K_1") (pintype "passive"))
      (node (ref "U2") (pin "2") (pinfunction "CHRG#_2") (pintype "passive"))
    )
    (net (code "32") (name "Net-(LED2-K)") (class "Default")
      (node (ref "LED2") (pin "1") (pinfunction "K_1") (pintype "passive"))
      (node (ref "U2") (pin "4") (pinfunction "STDBY#_4") (pintype "passive"))
    )
    (net (code "33") (name "Net-(LED3-A)") (class "Default")
      (node (ref "LED3") (pin "2") (pinfunction "A_2") (pintype "passive"))
      (node (ref "R11") (pin "1") (pinfunction "1_1") (pintype "passive"))
    )
    (net (code "34") (name "Net-(LED4-K)") (class "Default")
      (node (ref "LED4") (pin "1") (pinfunction "K_1") (pintype "passive"))
      (node (ref "R18") (pin "2") (pinfunction "2_2") (pintype "passive"))
    )
    (net (code "35") (name "Net-(LED5-K)") (class "Default")
      (node (ref "LED5") (pin "1") (pinfunction "K_1") (pintype "passive"))
      (node (ref "R19") (pin "2") (pinfunction "2_2") (pintype "passive"))
    )
    (net (code "36") (name "Net-(Q1-B)") (class "Default")
      (node (ref "Q1") (pin "1") (pinfunction "B_1") (pintype "passive"))
      (node (ref "R1") (pin "1") (pinfunction "1_1") (pintype "passive"))
    )
    (net (code "37") (name "Net-(Q2-B)") (class "Default")
      (node (ref "Q2") (pin "1") (pinfunction "B_1") (pintype "passive"))
      (node (ref "R6") (pin "1") (pinfunction "1_1") (pintype "passive"))
    )
    (net (code "38") (name "Net-(Q3-G)") (class "Default")
      (node (ref "Q3") (pin "1") (pinfunction "G_1") (pintype "passive"))
      (node (ref "R13") (pin "1") (pinfunction "1_1") (pintype "passive"))
      (node (ref "SW4") (pin "2") (pinfunction "2_2") (pintype "passive"))
    )
    (net (code "39") (name "Net-(R14-Pad1)") (class "Default")
      (node (ref "R14") (pin "1") (pinfunction "1_1") (pintype "passive"))
      (node (ref "R15") (pin "1") (pinfunction "1_1") (pintype "passive"))
      (node (ref "R16") (pin "1") (pinfunction "1_1") (pintype "passive"))
    )
    (net (code "40") (name "Net-(U1-IO8)") (class "Default")
      (node (ref "R7") (pin "2") (pinfunction "2_2") (pintype "passive"))
      (node (ref "U1") (pin "10") (pinfunction "IO8_10") (pintype "passive"))
    )
    (net (code "41") (name "Net-(U2-PROG)") (class "Default")
      (node (ref "R10") (pin "2") (pinfunction "2_2") (pintype "passive"))
      (node (ref "U2") (pin "3") (pinfunction "PROG_3") (pintype "passive"))
    )
    (net (code "42") (name "Net-(U2-VCC)") (class "Default")
      (node (ref "C5") (pin "2") (pinfunction "2_2") (pintype "passive"))
      (node (ref "R4") (pin "1") (pinfunction "1_1") (pintype "passive"))
      (node (ref "R5") (pin "2") (pinfunction "2_2") (pintype "passive"))
      (node (ref "U2") (pin "5") (pinfunction "VCC_5") (pintype "passive"))
    )
    (net (code "43") (name "Net-(U3-V3)") (class "Default")
      (node (ref "C9") (pin "2") (pinfunction "2_2") (pintype "passive"))
      (node (ref "U3") (pin "4") (pinfunction "V3_4") (pintype "passive"))
    )
    (net (code "44") (name "Net-(U4-EP)") (class "Default")
      (node (ref "C11") (pin "2") (pinfunction "2_2") (pintype "passive"))
      (node (ref "C15") (pin "1") (pinfunction "1_1") (pintype "passive"))
      (node (ref "PWR1") (pin "2") (pinfunction "2_2") (pintype "passive"))
      (node (ref "U4") (pin "5") (pinfunction "GND_5") (pintype "passive"))
      (node (ref "U4") (pin "7") (pinfunction "GND_7") (pintype "passive"))
      (node (ref "U4") (pin "8") (pinfunction "GND_8") (pintype "passive"))
      (node (ref "U4") (pin "9") (pinfunction "EP_9") (pintype "passive"))
    )
    (net (code "45") (name "Net-(U4-VDD)") (class "Default")
      (node (ref "C11") (pin "1") (pinfunction "1_1") (pintype "passive"))
      (node (ref "R12") (pin "2") (pinfunction "2_2") (pintype "passive"))
      (node (ref "U4") (pin "6") (pinfunction "VDD_6") (pintype "passive"))
    )
    (net (code "46") (name "Net-(U6-BST)") (class "Default")
      (node (ref "C12") (pin "1") (pinfunction "1_1") (pintype "passive"))
      (node (ref "U6") (pin "6") (pinfunction "BST_6") (pintype "passive"))
    )
    (net (code "47") (name "Net-(U6-SW)") (class "Default")
      (node (ref "C12") (pin "2") (pinfunction "2_2") (pintype "passive"))
      (node (ref "L2") (pin "1") (pinfunction "1_1") (pintype "passive"))
      (node (ref "U6") (pin "5") (pinfunction "SW_5") (pintype "passive"))
    )
    (net (code "48") (name "Net-(USB1-CC1)") (class "Default")
      (node (ref "R8") (pin "2") (pinfunction "2_2") (pintype "passive"))
      (node (ref "USB1") (pin "A5") (pinfunction "CC1_A5") (pintype "passive"))
    )
    (net (code "49") (name "Net-(USB1-CC2)") (class "Default")
      (node (ref "R9") (pin "2") (pinfunction "2_2") (pintype "passive"))
      (node (ref "USB1") (pin "B5") (pinfunction "CC2_B5") (pintype "passive"))
    )
    (net (code "50") (name "Net-(USB2-CC1)") (class "Default")
      (node (ref "R17") (pin "2") (pinfunction "2_2") (pintype "passive"))
      (node (ref "USB2") (pin "A5") (pinfunction "CC1_A5") (pintype "passive"))
    )
    (net (code "51") (name "Net-(USB2-CC2)") (class "Default")
      (node (ref "R20") (pin "2") (pinfunction "2_2") (pintype "passive"))
      (node (ref "USB2") (pin "B5") (pinfunction "CC2_B5") (pintype "passive"))
    )
    (net (code "52") (name "PW_5V") (class "Default")
      (node (ref "C3") (pin "2") (pinfunction "2_2") (pintype "passive"))
      (node (ref "C4") (pin "1") (pinfunction "1_1") (pintype "passive"))
      (node (ref "D2") (pin "1") (pinfunction "K_1") (pintype "passive"))
      (node (ref "D3") (pin "1") (pinfunction "K_1") (pintype "passive"))
      (node (ref "Q3") (pin "2") (pinfunction "S_2") (pintype "passive"))
      (node (ref "R13") (pin "2") (pinfunction "2_2") (pintype "passive"))
      (node (ref "SW4") (pin "1") (pinfunction "1_1") (pintype "passive"))
      (node (ref "U2") (pin "1") (pinfunction "VOUT_1") (pintype "passive"))
    )
    (net (code "53") (name "PW_BAT4.2V") (class "Default")
      (node (ref "C6") (pin "2") (pinfunction "2_2") (pintype "passive"))
      (node (ref "C7") (pin "2") (pinfunction "2_2") (pintype "passive"))
      (node (ref "C8") (pin "1") (pinfunction "1_1") (pintype "passive"))
      (node (ref "L1") (pin "1") (pinfunction "1_1") (pintype "passive"))
      (node (ref "PWR1") (pin "1") (pinfunction "1_1") (pintype "passive"))
      (node (ref "R12") (pin "1") (pinfunction "1_1") (pintype "passive"))
      (node (ref "R14") (pin "2") (pinfunction "2_2") (pintype "passive"))
      (node (ref "U2") (pin "6") (pinfunction "BAT_6") (pintype "passive"))
    )
    (net (code "54") (name "PW_D3.3V") (class "Default")
      (node (ref "C1") (pin "2") (pinfunction "2_2") (pintype "passive"))
      (node (ref "C10") (pin "2") (pinfunction "2_2") (pintype "passive"))
      (node (ref "C13") (pin "2") (pinfunction "2_2") (pintype "passive"))
      (node (ref "C14") (pin "2") (pinfunction "2_2") (pintype "passive"))
      (node (ref "C17") (pin "2") (pinfunction "2_2") (pintype "passive"))
      (node (ref "C18") (pin "2") (pinfunction "2_2") (pintype "passive"))
      (node (ref "C2") (pin "2") (pinfunction "2_2") (pintype "passive"))
      (node (ref "L2") (pin "2") (pinfunction "2_2") (pintype "passive"))
      (node (ref "R2") (pin "1") (pinfunction "1_1") (pintype "passive"))
      (node (ref "R3") (pin "1") (pinfunction "1_1") (pintype "passive"))
      (node (ref "R7") (pin "1") (pinfunction "1_1") (pintype "passive"))
      (node (ref "U1") (pin "2") (pinfunction "3V3_2") (pintype "passive"))
      (node (ref "U3") (pin "16") (pinfunction "VCC_16") (pintype "passive"))
      (node (ref "U5") (pin "3") (pinfunction "3_3") (pintype "passive"))
      (node (ref "U5") (pin "6") (pinfunction "6_6") (pintype "passive"))
      (node (ref "U6") (pin "1") (pinfunction "FB_1") (pintype "passive"))
    )
    (net (code "55") (name "PW_D5V") (class "Default")
      (node (ref "C16") (pin "1") (pinfunction "1_1") (pintype "passive"))
      (node (ref "D4") (pin "1") (pinfunction "K_1") (pintype "passive"))
      (node (ref "D5") (pin "1") (pinfunction "K_1") (pintype "passive"))
      (node (ref "U6") (pin "2") (pinfunction "EN_2") (pintype "passive"))
      (node (ref "U6") (pin "3") (pinfunction "VIN_3") (pintype "passive"))
    )
    (net (code "56") (name "PW_USB5V") (class "Default")
      (node (ref "D5") (pin "2") (pinfunction "A_2") (pintype "passive"))
      (node (ref "F1") (pin "2") (pinfunction "2_2") (pintype "passive"))
      (node (ref "F2") (pin "2") (pinfunction "2_2") (pintype "passive"))
      (node (ref "R4") (pin "2") (pinfunction "2_2") (pintype "passive"))
    )
    (net (code "57") (name "unconnected-(U1-IO3-Pad26)") (class "Default")
      (node (ref "U1") (pin "26") (pinfunction "IO3_26") (pintype "passive+no_connect"))
    )
    (net (code "58") (name "unconnected-(U1-IO4-Pad4)") (class "Default")
      (node (ref "U1") (pin "4") (pinfunction "IO4_4") (pintype "passive+no_connect"))
    )
    (net (code "59") (name "unconnected-(U1-IO5-Pad5)") (class "Default")
      (node (ref "U1") (pin "5") (pinfunction "IO5_5") (pintype "passive+no_connect"))
    )
    (net (code "60") (name "unconnected-(U1-IO6-Pad6)") (class "Default")
      (node (ref "U1") (pin "6") (pinfunction "IO6_6") (pintype "passive+no_connect"))
    )
    (net (code "61") (name "unconnected-(U1-IO15-Pad23)") (class "Default")
      (node (ref "U1") (pin "23") (pinfunction "IO15_23") (pintype "passive+no_connect"))
    )
    (net (code "62") (name "unconnected-(U1-NC-Pad22)") (class "Default")
      (node (ref "U1") (pin "22") (pinfunction "NC_22") (pintype "passive+no_connect"))
    )
    (net (code "63") (name "unconnected-(U3-CTS#-Pad9)") (class "Default")
      (node (ref "U3") (pin "9") (pinfunction "CTS#_9") (pintype "passive+no_connect"))
    )
    (net (code "64") (name "unconnected-(U3-DCD#-Pad12)") (class "Default")
      (node (ref "U3") (pin "12") (pinfunction "DCD#_12") (pintype "passive+no_connect"))
    )
    (net (code "65") (name "unconnected-(U3-DSR#-Pad10)") (class "Default")
      (node (ref "U3") (pin "10") (pinfunction "DSR#_10") (pintype "passive+no_connect"))
    )
    (net (code "66") (name "unconnected-(U3-NC.-Pad7)") (class "Default")
      (node (ref "U3") (pin "7") (pinfunction "NC._7") (pintype "passive+no_connect"))
    )
    (net (code "67") (name "unconnected-(U3-OUT#-Pad8)") (class "Default")
      (node (ref "U3") (pin "8") (pinfunction "OUT#_8") (pintype "passive+no_connect"))
    )
    (net (code "68") (name "unconnected-(U3-R232-Pad15)") (class "Default")
      (node (ref "U3") (pin "15") (pinfunction "R232_15") (pintype "passive+no_connect"))
    )
    (net (code "69") (name "unconnected-(U3-RI#-Pad11)") (class "Default")
      (node (ref "U3") (pin "11") (pinfunction "RI#_11") (pintype "passive+no_connect"))
    )
    (net (code "70") (name "unconnected-(U4-NC-Pad1)") (class "Default")
      (node (ref "U4") (pin "1") (pinfunction "NC_1") (pintype "passive+no_connect"))
    )
    (net (code "71") (name "unconnected-(USB1-SUB1-PadA8)") (class "Default")
      (node (ref "USB1") (pin "A8") (pinfunction "SUB1_A8") (pintype "passive+no_connect"))
    )
    (net (code "72") (name "unconnected-(USB1-SUB2-PadB8)") (class "Default")
      (node (ref "USB1") (pin "B8") (pinfunction "SUB2_B8") (pintype "passive+no_connect"))
    )
    (net (code "73") (name "unconnected-(USB2-SUB1-PadA8)") (class "Default")
      (node (ref "USB2") (pin "A8") (pinfunction "SUB1_A8") (pintype "passive+no_connect"))
    )
    (net (code "74") (name "unconnected-(USB2-SUB2-PadB8)") (class "Default")
      (node (ref "USB2") (pin "B8") (pinfunction "SUB2_B8") (pintype "passive+no_connect"))
    )
  )
)
